# Connectors.net
KiCad netlist of a schematic drawn in Altium Designer
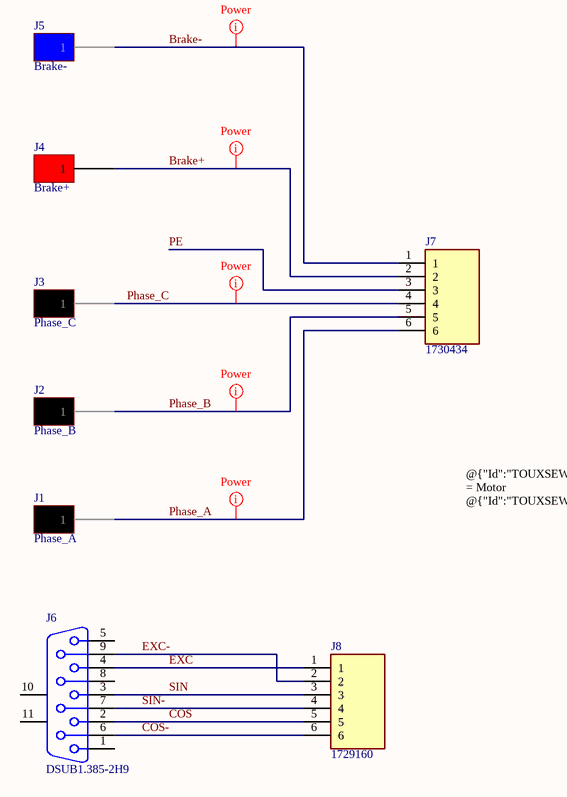
[diagram p0: Connectors.SchDoc]

(export (version "E")
  (design (tool "Eeschema 10.0.6"))
  (components
    (comp (ref "J1")
      (value "Phase_A")
      (footprint "FCR7350")
      (description "FCR7350B, 1000V, 24A, BLACK")
      (fields
        (field (name "MANUFACTURER PART NUMBER") "FCR7350B")
        (field (name "MANUFACTURER") "Cliff")
        (field (name "CREATED FROM") "DHufnagel")
      )
      (libsource (lib "user") (part "FCR7350B"))
    )
    (comp (ref "J2")
      (value "Phase_B")
      (footprint "FCR7350")
      (description "FCR7350B, 1000V, 24A, BLACK")
      (fields
        (field (name "MANUFACTURER PART NUMBER") "FCR7350B")
        (field (name "MANUFACTURER") "Cliff")
        (field (name "CREATED FROM") "DHufnagel")
      )
      (libsource (lib "user") (part "FCR7350B"))
    )
    (comp (ref "J3")
      (value "Phase_C")
      (footprint "FCR7350")
      (description "FCR7350B, 1000V, 24A, BLACK")
      (fields
        (field (name "MANUFACTURER PART NUMBER") "FCR7350B")
        (field (name "MANUFACTURER") "Cliff")
        (field (name "CREATED FROM") "DHufnagel")
      )
      (libsource (lib "user") (part "FCR7350B"))
    )
    (comp (ref "J4")
      (value "Brake+")
      (footprint "FCR7350")
      (description "FCR7350B, 1000V, 24A, RED")
      (fields
        (field (name "MANUFACTURER PART NUMBER") "FCR7350R")
        (field (name "MANUFACTURER") "Cliff")
        (field (name "CREATED FROM") "DHufnagel")
      )
      (libsource (lib "user") (part "FCR7350R"))
    )
    (comp (ref "J5")
      (value "Brake-")
      (footprint "FCR7350")
      (description "FCR7350B, 1000V, 24A, BLUE")
      (fields
        (field (name "MANUFACTURER PART NUMBER") "FCR7350L")
        (field (name "MANUFACTURER") "Cliff")
        (field (name "CREATED FROM") "DHufnagel")
      )
      (libsource (lib "user") (part "FCR7350L"))
    )
    (comp (ref "J6")
      (value "DSUB1.385-2H9")
      (footprint "DSUB1.385-2H9")
      (description "Connector; D Subminiature; 9 Position; Right Angle; Pitch 1.385 mm")
      (fields
        (field (name "MANUFACTURER") "TE Connectivity")
        (field (name "LCSC PART NUMBER") "C141882")
        (field (name "PUBLISHER") "Altium Limited")
        (field (name "CREATED FROM") "MHlatky")
      )
      (libsource (lib "user") (part "D Connector 9"))
    )
    (comp (ref "J7")
      (value "1730434")
      (footprint "1730434")
      (description "Fixed Mounting Block, 6 Pins, 5.08mm Pitch, 26-14 AWG")
      (fields (field (name "MANUFACTURER") "Phoenix Contact") (field (name "CREATED FROM") "DHufnagel"))
      (libsource (lib "user") (part "1730434"))
    )
    (comp (ref "J8")
      (value "1729160")
      (footprint "1729160")
      (description "Fixed Mounting Block, 6 Pins, 5.08mm Pitch, 26-16 AWG")
      (fields (field (name "MANUFACTURER") "Phoenix Contact") (field (name "CREATED FROM") "DHufnagel"))
      (libsource (lib "user") (part "1729160"))
    )
  )
  (nets
    (net (code "1") (name "/Brake+") (class "Default")
      (node (ref "J4") (pin "1") (pinfunction "1_1") (pintype "passive"))
      (node (ref "J7") (pin "2") (pinfunction "2_2") (pintype "passive"))
    )
    (net (code "2") (name "/Brake-") (class "Default")
      (node (ref "J5") (pin "1") (pinfunction "1_1") (pintype "passive"))
      (node (ref "J7") (pin "1") (pinfunction "1_1") (pintype "passive"))
    )
    (net (code "3") (name "/COS") (class "Default")
      (node (ref "J6") (pin "2") (pinfunction "2_2") (pintype "passive"))
      (node (ref "J8") (pin "5") (pinfunction "5_5") (pintype "passive"))
    )
    (net (code "4") (name "/COS-") (class "Default")
      (node (ref "J6") (pin "6") (pinfunction "6_6") (pintype "passive"))
      (node (ref "J8") (pin "6") (pinfunction "6_6") (pintype "passive"))
    )
    (net (code "5") (name "/EXC") (class "Default")
      (node (ref "J6") (pin "4") (pinfunction "4_4") (pintype "passive"))
      (node (ref "J8") (pin "1") (pinfunction "1_1") (pintype "passive"))
    )
    (net (code "6") (name "/EXC-") (class "Default")
      (node (ref "J6") (pin "9") (pinfunction "9_9") (pintype "passive"))
      (node (ref "J8") (pin "2") (pinfunction "2_2") (pintype "passive"))
    )
    (net (code "7") (name "/PE") (class "Default")
      (node (ref "J7") (pin "3") (pinfunction "3_3") (pintype "passive"))
    )
    (net (code "8") (name "/Phase_A") (class "Default")
      (node (ref "J1") (pin "1") (pinfunction "1_1") (pintype "passive"))
      (node (ref "J7") (pin "6") (pinfunction "6_6") (pintype "passive"))
    )
    (net (code "9") (name "/Phase_B") (class "Default")
      (node (ref "J2") (pin "1") (pinfunction "1_1") (pintype "passive"))
      (node (ref "J7") (pin "5") (pinfunction "5_5") (pintype "passive"))
    )
    (net (code "10") (name "/Phase_C") (class "Default")
      (node (ref "J3") (pin "1") (pinfunction "1_1") (pintype "passive"))
      (node (ref "J7") (pin "4") (pinfunction "4_4") (pintype "passive"))
    )
    (net (code "11") (name "/SIN") (class "Default")
      (node (ref "J6") (pin "3") (pinfunction "3_3") (pintype "passive"))
      (node (ref "J8") (pin "3") (pinfunction "3_3") (pintype "passive"))
    )
    (net (code "12") (name "/SIN-") (class "Default")
      (node (ref "J6") (pin "7") (pinfunction "7_7") (pintype "passive"))
      (node (ref "J8") (pin "4") (pinfunction "4_4") (pintype "passive"))
    )
    (net (code "13") (name "unconnected-(J6-MH1-Pad10)") (class "Default")
      (node (ref "J6") (pin "10") (pinfunction "MH1_10") (pintype "passive"))
    )
    (net (code "14") (name "unconnected-(J6-MH2-Pad11)") (class "Default")
      (node (ref "J6") (pin "11") (pinfunction "MH2_11") (pintype "passive"))
    )
    (net (code "15") (name "unconnected-(J6-Pad1)") (class "Default")
      (node (ref "J6") (pin "1") (pinfunction "1_1") (pintype "passive"))
    )
    (net (code "16") (name "unconnected-(J6-Pad5)") (class "Default")
      (node (ref "J6") (pin "5") (pinfunction "5_5") (pintype "passive"))
    )
    (net (code "17") (name "unconnected-(J6-Pad8)") (class "Default")
      (node (ref "J6") (pin "8") (pinfunction "8_8") (pintype "passive"))
    )
  )
)
